# 2-LCD_CAMERA.net
KiCad netlist of a schematic drawn in Altium Designer
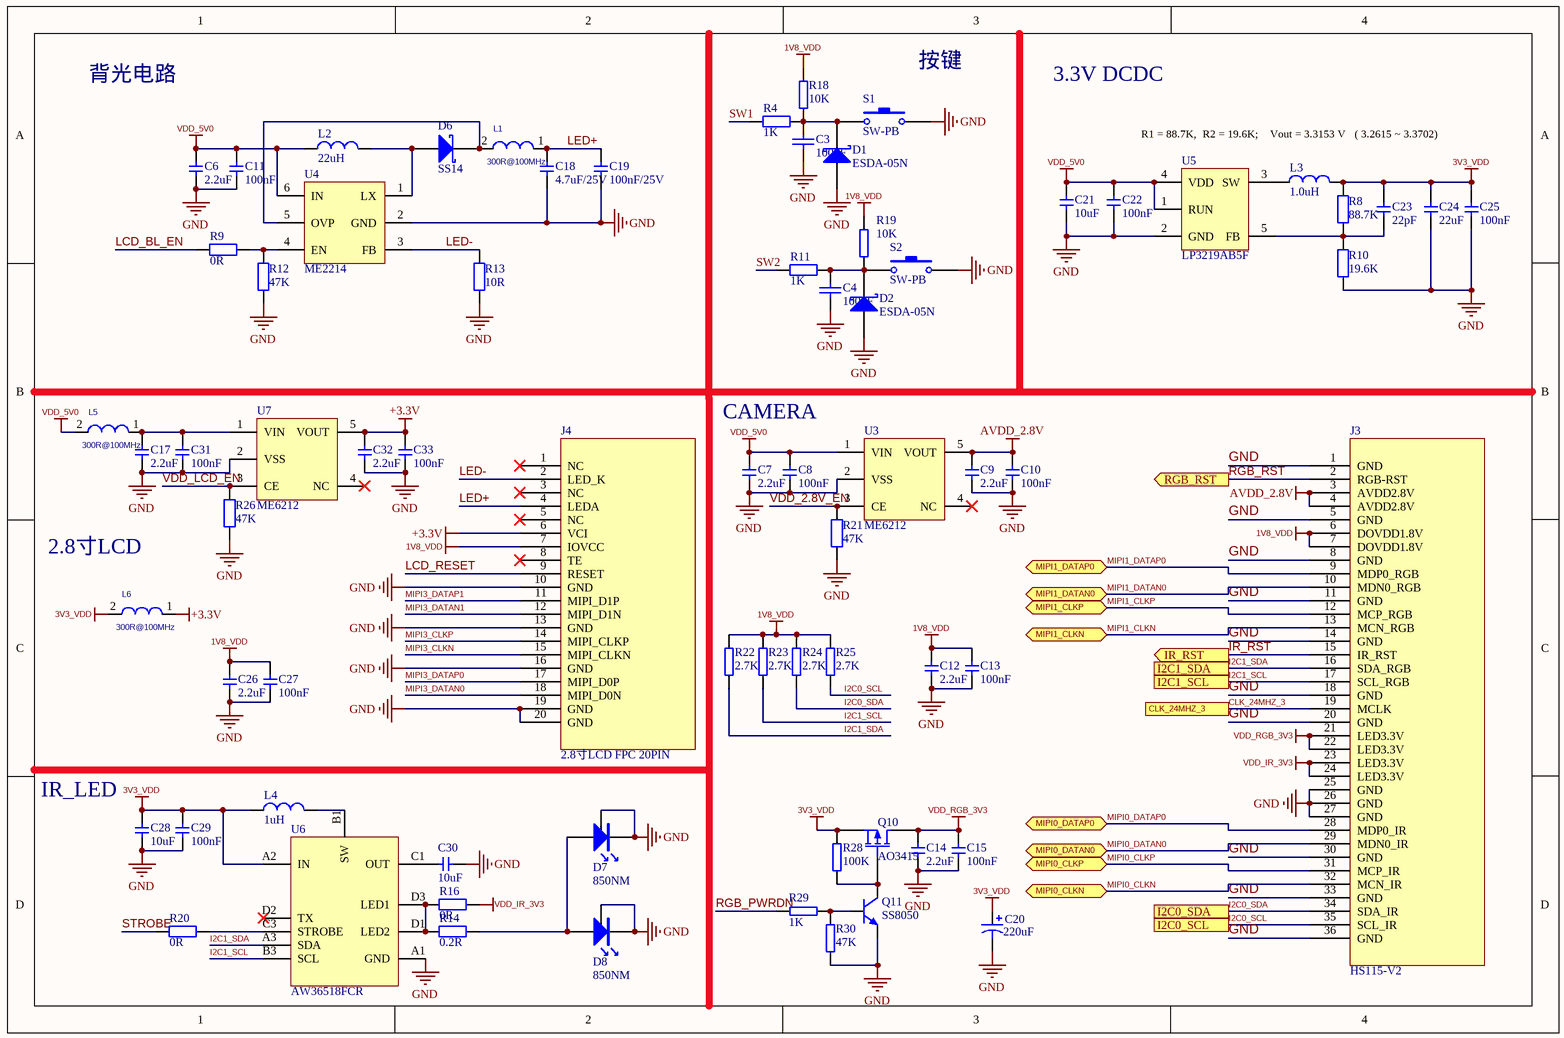
[diagram p0: 2-LCD&CAMERA.SchDoc]

(export (version "E")
  (design (tool "Eeschema 10.0.6"))
  (components
    (comp (ref "C3")
      (value "100nF")
      (footprint "C0402")
      (description "Capacitor")
      (libsource (lib "LORATEMPSENSOR_V0.02") (part "Cap"))
    )
    (comp (ref "C4")
      (value "100nF")
      (footprint "C0402")
      (description "Capacitor")
      (libsource (lib "LORATEMPSENSOR_V0.02") (part "Cap"))
    )
    (comp (ref "C6")
      (value "2.2uF")
      (footprint "C0402")
      (description "C?")
      (libsource (lib "HNCY_SCH_Lib") (part "CAP1"))
    )
    (comp (ref "C7")
      (value "2.2uF")
      (footprint "C0402")
      (description "C?")
      (libsource (lib "HNCY_SCH_Lib") (part "CAP1"))
    )
    (comp (ref "C8")
      (value "100nF")
      (footprint "C0402")
      (description "C?")
      (libsource (lib "HNCY_SCH_Lib") (part "CAP1"))
    )
    (comp (ref "C9")
      (value "2.2uF")
      (footprint "C0402")
      (description "C?")
      (libsource (lib "HNCY_SCH_Lib") (part "CAP1"))
    )
    (comp (ref "C10")
      (value "100nF")
      (footprint "C0402")
      (description "C?")
      (libsource (lib "HNCY_SCH_Lib") (part "CAP1"))
    )
    (comp (ref "C11")
      (value "100nF")
      (footprint "C0402")
      (description "C?")
      (libsource (lib "HNCY_SCH_Lib") (part "CAP1"))
    )
    (comp (ref "C12")
      (value "2.2uF")
      (footprint "C0402")
      (description "C?")
      (libsource (lib "HNCY_SCH_Lib") (part "CAP1"))
    )
    (comp (ref "C13")
      (value "100nF")
      (footprint "C0402")
      (description "C?")
      (libsource (lib "HNCY_SCH_Lib") (part "CAP1"))
    )
    (comp (ref "C14")
      (value "2.2uF")
      (footprint "C0402")
      (description "C?")
      (libsource (lib "HNCY_SCH_Lib") (part "CAP1"))
    )
    (comp (ref "C15")
      (value "100nF")
      (footprint "C0402")
      (description "C?")
      (libsource (lib "HNCY_SCH_Lib") (part "CAP1"))
    )
    (comp (ref "C17")
      (value "2.2uF")
      (footprint "C0402")
      (description "C?")
      (libsource (lib "HNCY_SCH_Lib") (part "CAP1"))
    )
    (comp (ref "C18")
      (value "4.7uF/25V")
      (footprint "Cap_0603")
      (description "C?")
      (libsource (lib "HNCY_SCH_Lib") (part "CAP1"))
    )
    (comp (ref "C19")
      (value "100nF/25V")
      (footprint "C0402")
      (description "C?")
      (libsource (lib "HNCY_SCH_Lib") (part "CAP1"))
    )
    (comp (ref "C20")
      (value "220uF")
      (footprint "SMD,6.3x7.7mm")
      (description "Polarized Capacitor (Radial)")
      (fields (field (name "Comment") "Cap Pol1") (field (name "PUBLISHER") "Altium Limited"))
      (libsource (lib "Miscellaneous Devices") (part "Cap Pol1"))
    )
    (comp (ref "C21")
      (value "10uF")
      (footprint "Cap_0603")
      (description "C?")
      (libsource (lib "HNCY_SCH_Lib") (part "CAP1"))
    )
    (comp (ref "C22")
      (value "100nF")
      (footprint "C0402")
      (description "C?")
      (libsource (lib "HNCY_SCH_Lib") (part "CAP1"))
    )
    (comp (ref "C23")
      (value "22pF")
      (footprint "C0402")
      (description "C?")
      (libsource (lib "HNCY_SCH_Lib") (part "CAP1"))
    )
    (comp (ref "C24")
      (value "22uF")
      (footprint "CAP_0603")
      (description "C?")
      (libsource (lib "HNCY_SCH_Lib") (part "CAP1"))
    )
    (comp (ref "C25")
      (value "100nF")
      (footprint "C0402")
      (description "C?")
      (libsource (lib "HNCY_SCH_Lib") (part "CAP1"))
    )
    (comp (ref "C26")
      (value "2.2uF")
      (footprint "C0402")
      (description "C?")
      (libsource (lib "HNCY_SCH_Lib") (part "CAP1"))
    )
    (comp (ref "C27")
      (value "100nF")
      (footprint "C0402")
      (description "C?")
      (libsource (lib "HNCY_SCH_Lib") (part "CAP1"))
    )
    (comp (ref "C28")
      (value "10uF")
      (footprint "C0402")
      (description "C?")
      (libsource (lib "HNCY_SCH_Lib") (part "CAP1"))
    )
    (comp (ref "C29")
      (value "100nF")
      (footprint "C0402")
      (description "C?")
      (libsource (lib "HNCY_SCH_Lib") (part "CAP1"))
    )
    (comp (ref "C30")
      (value "10uF")
      (footprint "C0402")
      (description "C?")
      (libsource (lib "HNCY_SCH_Lib") (part "CAP1"))
    )
    (comp (ref "C31")
      (value "100nF")
      (footprint "C0402")
      (description "C?")
      (libsource (lib "HNCY_SCH_Lib") (part "CAP1"))
    )
    (comp (ref "C32")
      (value "2.2uF")
      (footprint "C0402")
      (description "C?")
      (libsource (lib "HNCY_SCH_Lib") (part "CAP1"))
    )
    (comp (ref "C33")
      (value "100nF")
      (footprint "C0402")
      (description "C?")
      (libsource (lib "HNCY_SCH_Lib") (part "CAP1"))
    )
    (comp (ref "D1")
      (value "ESDA-05N")
      (footprint "R0402")
      (description "Silicon AF Schottky Diode for High-Speed Switching")
      (fields (field (name "PUBLISHER") "Altium Limited"))
      (libsource (lib "Miscellaneous Devices") (part "Diode BAS70"))
    )
    (comp (ref "D2")
      (value "ESDA-05N")
      (footprint "R0402")
      (description "Silicon AF Schottky Diode for High-Speed Switching")
      (fields (field (name "PUBLISHER") "Altium Limited"))
      (libsource (lib "Miscellaneous Devices") (part "Diode BAS70"))
    )
    (comp (ref "D6")
      (value "SS14")
      (footprint "SOD-123F")
      (description "Silicon AF Schottky Diode for High-Speed Switching")
      (fields (field (name "PUBLISHER") "Altium Limited"))
      (libsource (lib "Miscellaneous Devices") (part "Diode BAS70"))
    )
    (comp (ref "D7")
      (value "850NM")
      (footprint "LED-3535-850MM")
      (description "贴片LED，3535，红外850NM")
      (libsource (lib "MY SCHLIB") (part "LED_IR"))
    )
    (comp (ref "D8")
      (value "850NM")
      (footprint "LED-3535-850MM")
      (description "贴片LED，3535，红外850NM")
      (libsource (lib "Common") (part "LED_IR"))
    )
    (comp (ref "J3")
      (value "HS115-V2")
      (footprint "0.5-36PIN")
      (libsource (lib "MY SCHLIB") (part "HS115-V2"))
    )
    (comp (ref "J4")
      (value "2.8寸LCD FPC 20PIN")
      (footprint "0.5-20PIN-抽屉上接")
      (description "1-Lane MIPI")
      (libsource (lib "MY SCHLIB") (part "2.8寸LCD FPC 20PIN"))
    )
    (comp (ref "L1") (value "300R@100MHz") (footprint "Res_0603") (libsource (lib "*") (part "L/0402")))
    (comp (ref "L2") (value "22uH") (footprint "L3*3") (libsource (lib "封装") (part "LineInductors")))
    (comp (ref "L3")
      (value "1.0uH")
      (footprint "L2.5x2.0x1.0mm")
      (libsource (lib "封装") (part "LineInductors"))
    )
    (comp (ref "L4") (value "1uH") (footprint "L2.5x2.0x1.0mm") (libsource (lib "封装") (part "LineInductors")))
    (comp (ref "L5") (value "300R@100MHz") (footprint "Res_0603") (libsource (lib "*") (part "L/0402")))
    (comp (ref "L6") (value "300R@100MHz") (footprint "Res_0603") (libsource (lib "*") (part "L/0402")))
    (comp (ref "Q10") (value "AO3415") (footprint "SOT-23") (libsource (lib "*") (part "AO3415")))
    (comp (ref "Q11")
      (value "SS8050")
      (footprint "SOT23-BEC")
      (description "贴片三极管")
      (libsource (lib "HNCY_SCH_Lib") (part "NPN"))
    )
    (comp (ref "R4")
      (value "1K")
      (footprint "R0402")
      (description "Resistor")
      (fields (field (name "PUBLISHER") "Altium Limited"))
      (libsource (lib "") (part "Res2_1"))
    )
    (comp (ref "R8")
      (value "88.7K")
      (footprint "R0402")
      (description "Resistor")
      (fields (field (name "PUBLISHER") "Altium Limited"))
      (libsource (lib "Miscellaneous Devices") (part "Res2"))
    )
    (comp (ref "R9")
      (value "0R")
      (footprint "R0402")
      (description "Resistor")
      (fields (field (name "PUBLISHER") "Altium Limited"))
      (libsource (lib "") (part "Res2_1"))
    )
    (comp (ref "R10")
      (value "19.6K")
      (footprint "R0402")
      (description "Resistor")
      (fields (field (name "PUBLISHER") "Altium Limited"))
      (libsource (lib "") (part "Res2_2"))
    )
    (comp (ref "R11")
      (value "1K")
      (footprint "R0402")
      (description "Resistor")
      (fields (field (name "PUBLISHER") "Altium Limited"))
      (libsource (lib "") (part "Res2_1"))
    )
    (comp (ref "R12")
      (value "47K")
      (footprint "R0402")
      (description "Resistor")
      (fields (field (name "PUBLISHER") "Altium Limited"))
      (libsource (lib "Miscellaneous Devices") (part "Res2"))
    )
    (comp (ref "R13")
      (value "10R")
      (footprint "R0805")
      (description "Resistor")
      (fields (field (name "PUBLISHER") "Altium Limited"))
      (libsource (lib "") (part "Res2_2"))
    )
    (comp (ref "R14")
      (value "0.2R")
      (footprint "R0805")
      (description "Resistor")
      (fields (field (name "PUBLISHER") "Altium Limited"))
      (libsource (lib "") (part "Res2_1"))
    )
    (comp (ref "R16")
      (value "0R")
      (footprint "R0805")
      (description "Resistor")
      (fields (field (name "PUBLISHER") "Altium Limited"))
      (libsource (lib "") (part "Res2_1"))
    )
    (comp (ref "R18")
      (value "10K")
      (footprint "R0402")
      (description "R?")
      (libsource (lib "HNCY_SCH_Lib") (part "RES1"))
    )
    (comp (ref "R19")
      (value "10K")
      (footprint "R0402")
      (description "R?")
      (libsource (lib "HNCY_SCH_Lib") (part "RES1"))
    )
    (comp (ref "R20")
      (value "0R")
      (footprint "R0402")
      (description "Resistor")
      (fields (field (name "PUBLISHER") "Altium Limited"))
      (libsource (lib "") (part "Res2_1"))
    )
    (comp (ref "R21")
      (value "47K")
      (footprint "R0402")
      (description "Resistor")
      (fields (field (name "PUBLISHER") "Altium Limited"))
      (libsource (lib "Miscellaneous Devices") (part "Res2"))
    )
    (comp (ref "R22")
      (value "2.7K")
      (footprint "R0402")
      (description "R?")
      (libsource (lib "HNCY_SCH_Lib") (part "RES1"))
    )
    (comp (ref "R23")
      (value "2.7K")
      (footprint "R0402")
      (description "R?")
      (libsource (lib "HNCY_SCH_Lib") (part "RES1"))
    )
    (comp (ref "R24")
      (value "2.7K")
      (footprint "R0402")
      (description "R?")
      (libsource (lib "HNCY_SCH_Lib") (part "RES1"))
    )
    (comp (ref "R25")
      (value "2.7K")
      (footprint "R0402")
      (description "R?")
      (libsource (lib "HNCY_SCH_Lib") (part "RES1"))
    )
    (comp (ref "R26")
      (value "47K")
      (footprint "R0402")
      (description "Resistor")
      (fields (field (name "PUBLISHER") "Altium Limited"))
      (libsource (lib "Miscellaneous Devices") (part "Res2"))
    )
    (comp (ref "R28")
      (value "100K")
      (footprint "R0402")
      (description "R?")
      (libsource (lib "HNCY_SCH_Lib") (part "RES1"))
    )
    (comp (ref "R29")
      (value "1K")
      (footprint "R0402")
      (description "R?")
      (libsource (lib "HNCY_SCH_Lib") (part "RES1"))
    )
    (comp (ref "R30")
      (value "47K")
      (footprint "R0402")
      (description "R?")
      (libsource (lib "HNCY_SCH_Lib") (part "RES1"))
    )
    (comp (ref "S1")
      (value "SW-PB")
      (footprint "轻触开关4.5x4.5")
      (description "Switch")
      (fields (field (name "PUBLISHER") "Altium Limited"))
      (libsource (lib "Miscellaneous Devices") (part "SW-PB"))
    )
    (comp (ref "S2")
      (value "SW-PB")
      (footprint "轻触开关4.5x4.5")
      (description "Switch")
      (fields (field (name "PUBLISHER") "Altium Limited"))
      (libsource (lib "Miscellaneous Devices") (part "SW-PB"))
    )
    (comp (ref "U3") (value "ME6212") (footprint "SOT23-5") (libsource (lib "MY SCHLIB") (part "ME6212")))
    (comp (ref "U4") (value "ME2214") (footprint "SOT26") (libsource (lib "MY SCHLIB") (part "ME2214")))
    (comp (ref "U5") (value "LP3219AB5F") (footprint "SOT23-5") (libsource (lib "MY SCHLIB") (part "TD6817")))
    (comp (ref "U6")
      (value "AW36518FCR")
      (footprint "FCQFN-10L")
      (libsource (lib "MY SCHLIB") (part "AW36518FCR"))
    )
    (comp (ref "U7") (value "ME6212") (footprint "SOT23-5") (libsource (lib "MY SCHLIB") (part "ME6212")))
  )
  (nets
    (net (code "1") (name "+3.3V") (class "Default")
      (node (ref "C32") (pin "1") (pintype "passive"))
      (node (ref "C33") (pin "1") (pintype "passive"))
      (node (ref "J4") (pin "6") (pinfunction "VCI_6") (pintype "passive"))
      (node (ref "L6") (pin "1") (pinfunction "1_1") (pintype "passive"))
      (node (ref "U7") (pin "5") (pinfunction "VOUT_5") (pintype "passive"))
    )
    (net (code "2") (name "/CLK_24MHZ_3") (class "Default")
      (node (ref "J3") (pin "19") (pinfunction "MCLK_19") (pintype "passive"))
    )
    (net (code "3") (name "/I2C0_SCL") (class "Default")
      (node (ref "J3") (pin "35") (pinfunction "SCL_IR_35") (pintype "passive"))
      (node (ref "R25") (pin "2") (pinfunction "2_2") (pintype "passive"))
    )
    (net (code "4") (name "/I2C0_SDA") (class "Default")
      (node (ref "J3") (pin "34") (pinfunction "SDA_IR_34") (pintype "passive"))
      (node (ref "R24") (pin "2") (pinfunction "2_2") (pintype "passive"))
    )
    (net (code "5") (name "/I2C1_SCL") (class "Default")
      (node (ref "J3") (pin "17") (pinfunction "SCL_RGB_17") (pintype "passive"))
      (node (ref "R23") (pin "2") (pinfunction "2_2") (pintype "passive"))
      (node (ref "U6") (pin "B3") (pinfunction "SCL_B3") (pintype "passive"))
    )
    (net (code "6") (name "/I2C1_SDA") (class "Default")
      (node (ref "J3") (pin "16") (pinfunction "SDA_RGB_16") (pintype "passive"))
      (node (ref "R22") (pin "2") (pinfunction "2_2") (pintype "passive"))
      (node (ref "U6") (pin "A3") (pinfunction "SDA_A3") (pintype "passive"))
    )
    (net (code "7") (name "/IR_RST") (class "Default")
      (node (ref "J3") (pin "15") (pinfunction "IR_RST_15") (pintype "passive"))
    )
    (net (code "8") (name "/LCD_BL_EN") (class "Default")
      (node (ref "R9") (pin "1") (pinfunction "1_1") (pintype "passive"))
    )
    (net (code "9") (name "/LCD_RESET") (class "Default")
      (node (ref "J4") (pin "9") (pinfunction "RESET_9") (pintype "passive"))
    )
    (net (code "10") (name "/LED+") (class "Default")
      (node (ref "C18") (pin "1") (pintype "passive"))
      (node (ref "C19") (pin "1") (pintype "passive"))
      (node (ref "J4") (pin "4") (pinfunction "LEDA_4") (pintype "passive"))
      (node (ref "L1") (pin "1") (pinfunction "1_1") (pintype "passive"))
    )
    (net (code "11") (name "/LED-") (class "Default")
      (node (ref "J4") (pin "2") (pinfunction "LED_K_2") (pintype "passive"))
      (node (ref "R13") (pin "1") (pinfunction "1_1") (pintype "passive"))
      (node (ref "U4") (pin "3") (pinfunction "FB_3") (pintype "passive"))
    )
    (net (code "12") (name "/MIPI0_CLKN") (class "Default")
      (node (ref "J3") (pin "32") (pinfunction "MCN_IR_32") (pintype "passive"))
    )
    (net (code "13") (name "/MIPI0_CLKP") (class "Default")
      (node (ref "J3") (pin "31") (pinfunction "MCP_IR_31") (pintype "passive"))
    )
    (net (code "14") (name "/MIPI0_DATAN0") (class "Default")
      (node (ref "J3") (pin "29") (pinfunction "MDN0_IR_29") (pintype "passive"))
    )
    (net (code "15") (name "/MIPI0_DATAP0") (class "Default")
      (node (ref "J3") (pin "28") (pinfunction "MDP0_IR_28") (pintype "passive"))
    )
    (net (code "16") (name "/MIPI1_CLKN") (class "Default")
      (node (ref "J3") (pin "13") (pinfunction "MCN_RGB_13") (pintype "passive"))
    )
    (net (code "17") (name "/MIPI1_CLKP") (class "Default")
      (node (ref "J3") (pin "12") (pinfunction "MCP_RGB_12") (pintype "passive"))
    )
    (net (code "18") (name "/MIPI1_DATAN0") (class "Default")
      (node (ref "J3") (pin "10") (pinfunction "MDN0_RGB_10") (pintype "passive"))
    )
    (net (code "19") (name "/MIPI1_DATAP0") (class "Default")
      (node (ref "J3") (pin "9") (pinfunction "MDP0_RGB_9") (pintype "passive"))
    )
    (net (code "20") (name "/MIPI3_CLKN") (class "Default")
      (node (ref "J4") (pin "15") (pinfunction "MIPI_CLKN_15") (pintype "passive"))
    )
    (net (code "21") (name "/MIPI3_CLKP") (class "Default")
      (node (ref "J4") (pin "14") (pinfunction "MIPI_CLKP_14") (pintype "passive"))
    )
    (net (code "22") (name "/MIPI3_DATAN0") (class "Default")
      (node (ref "J4") (pin "18") (pinfunction "MIPI_D0N_18") (pintype "passive"))
    )
    (net (code "23") (name "/MIPI3_DATAN1") (class "Default")
      (node (ref "J4") (pin "12") (pinfunction "MIPI_D1N_12") (pintype "passive"))
    )
    (net (code "24") (name "/MIPI3_DATAP0") (class "Default")
      (node (ref "J4") (pin "17") (pinfunction "MIPI_D0P_17") (pintype "passive"))
    )
    (net (code "25") (name "/MIPI3_DATAP1") (class "Default")
      (node (ref "J4") (pin "11") (pinfunction "MIPI_D1P_11") (pintype "passive"))
    )
    (net (code "26") (name "/RGB_PWRDN") (class "Default")
      (node (ref "R29") (pin "2") (pinfunction "2_2") (pintype "passive"))
    )
    (net (code "27") (name "/RGB_RST") (class "Default")
      (node (ref "J3") (pin "2") (pinfunction "RGB-RST_2") (pintype "passive"))
    )
    (net (code "28") (name "/STROBE") (class "Default")
      (node (ref "R20") (pin "1") (pinfunction "1_1") (pintype "passive"))
    )
    (net (code "29") (name "/SW1") (class "Default")
      (node (ref "R4") (pin "1") (pinfunction "1_1") (pintype "passive"))
    )
    (net (code "30") (name "/SW2") (class "Default")
      (node (ref "R11") (pin "1") (pinfunction "1_1") (pintype "passive"))
    )
    (net (code "31") (name "/VDD_2.8V_EN") (class "Default")
      (node (ref "R21") (pin "2") (pinfunction "2_2") (pintype "passive"))
      (node (ref "U3") (pin "3") (pinfunction "CE_3") (pintype "passive"))
    )
    (net (code "32") (name "/VDD_LCD_EN") (class "Default")
      (node (ref "R26") (pin "2") (pinfunction "2_2") (pintype "passive"))
      (node (ref "U7") (pin "3") (pinfunction "CE_3") (pintype "passive"))
    )
    (net (code "33") (name "1V8_VDD") (class "Default")
      (node (ref "C12") (pin "1") (pintype "passive"))
      (node (ref "C13") (pin "1") (pintype "passive"))
      (node (ref "C26") (pin "1") (pintype "passive"))
      (node (ref "C27") (pin "1") (pintype "passive"))
      (node (ref "J3") (pin "6") (pinfunction "DOVDD1.8V_6") (pintype "passive"))
      (node (ref "J3") (pin "7") (pinfunction "DOVDD1.8V_7") (pintype "passive"))
      (node (ref "J4") (pin "7") (pinfunction "IOVCC_7") (pintype "passive"))
      (node (ref "R18") (pin "2") (pinfunction "2_2") (pintype "passive"))
      (node (ref "R19") (pin "2") (pinfunction "2_2") (pintype "passive"))
      (node (ref "R22") (pin "1") (pinfunction "1_1") (pintype "passive"))
      (node (ref "R23") (pin "1") (pinfunction "1_1") (pintype "passive"))
      (node (ref "R24") (pin "1") (pinfunction "1_1") (pintype "passive"))
      (node (ref "R25") (pin "1") (pinfunction "1_1") (pintype "passive"))
    )
    (net (code "34") (name "3V3_VDD") (class "Default")
      (node (ref "C20") (pin "1") (pinfunction "1_1") (pintype "passive"))
      (node (ref "C23") (pin "2") (pintype "passive"))
      (node (ref "C24") (pin "1") (pintype "passive"))
      (node (ref "C25") (pin "1") (pintype "passive"))
      (node (ref "C28") (pin "1") (pintype "passive"))
      (node (ref "C29") (pin "1") (pintype "passive"))
      (node (ref "L3") (pin "2") (pinfunction "2_2") (pintype "passive"))
      (node (ref "L4") (pin "1") (pinfunction "1_1") (pintype "passive"))
      (node (ref "L6") (pin "2") (pinfunction "2_2") (pintype "passive"))
      (node (ref "Q10") (pin "2") (pinfunction "S_2") (pintype "passive"))
      (node (ref "R28") (pin "2") (pinfunction "2_2") (pintype "passive"))
      (node (ref "R8") (pin "2") (pinfunction "2_2") (pintype "passive"))
      (node (ref "U6") (pin "A2") (pinfunction "IN_A2") (pintype "passive"))
    )
    (net (code "35") (name "AVDD_2.8V") (class "Default")
      (node (ref "C10") (pin "1") (pintype "passive"))
      (node (ref "C9") (pin "1") (pintype "passive"))
      (node (ref "J3") (pin "3") (pinfunction "AVDD2.8V_3") (pintype "passive"))
      (node (ref "J3") (pin "4") (pinfunction "AVDD2.8V_4") (pintype "passive"))
      (node (ref "U3") (pin "5") (pinfunction "VOUT_5") (pintype "passive"))
    )
    (net (code "36") (name "GND") (class "Default")
      (node (ref "C10") (pin "2") (pintype "passive"))
      (node (ref "C11") (pin "2") (pintype "passive"))
      (node (ref "C12") (pin "2") (pintype "passive"))
      (node (ref "C13") (pin "2") (pintype "passive"))
      (node (ref "C14") (pin "2") (pintype "passive"))
      (node (ref "C15") (pin "2") (pintype "passive"))
      (node (ref "C17") (pin "2") (pintype "passive"))
      (node (ref "C18") (pin "2") (pintype "passive"))
      (node (ref "C19") (pin "2") (pintype "passive"))
      (node (ref "C20") (pin "2") (pinfunction "2_2") (pintype "passive"))
      (node (ref "C21") (pin "2") (pintype "passive"))
      (node (ref "C22") (pin "2") (pintype "passive"))
      (node (ref "C24") (pin "2") (pintype "passive"))
      (node (ref "C25") (pin "2") (pintype "passive"))
      (node (ref "C26") (pin "2") (pintype "passive"))
      (node (ref "C27") (pin "2") (pintype "passive"))
      (node (ref "C28") (pin "2") (pintype "passive"))
      (node (ref "C29") (pin "2") (pintype "passive"))
      (node (ref "C3") (pin "2") (pinfunction "2_2") (pintype "passive"))
      (node (ref "C30") (pin "2") (pintype "passive"))
      (node (ref "C31") (pin "2") (pintype "passive"))
      (node (ref "C32") (pin "2") (pintype "passive"))
      (node (ref "C33") (pin "2") (pintype "passive"))
      (node (ref "C4") (pin "2") (pinfunction "2_2") (pintype "passive"))
      (node (ref "C6") (pin "2") (pintype "passive"))
      (node (ref "C7") (pin "2") (pintype "passive"))
      (node (ref "C8") (pin "2") (pintype "passive"))
      (node (ref "C9") (pin "2") (pintype "passive"))
      (node (ref "D1") (pin "1") (pinfunction "A_1") (pintype "passive"))
      (node (ref "D2") (pin "1") (pinfunction "A_1") (pintype "passive"))
      (node (ref "D7") (pin "0") (pinfunction "0_0") (pintype "passive"))
      (node (ref "D7") (pin "K") (pinfunction "K_K") (pintype "passive"))
      (node (ref "D8") (pin "0") (pinfunction "0_0") (pintype "passive"))
      (node (ref "D8") (pin "K") (pinfunction "K_K") (pintype "passive"))
      (node (ref "J3") (pin "1") (pinfunction "GND_1") (pintype "passive"))
      (node (ref "J3") (pin "11") (pinfunction "GND_11") (pintype "passive"))
      (node (ref "J3") (pin "14") (pinfunction "GND_14") (pintype "passive"))
      (node (ref "J3") (pin "18") (pinfunction "GND_18") (pintype "passive"))
      (node (ref "J3") (pin "20") (pinfunction "GND_20") (pintype "passive"))
      (node (ref "J3") (pin "25") (pinfunction "GND_25") (pintype "passive"))
      (node (ref "J3") (pin "26") (pinfunction "GND_26") (pintype "passive"))
      (node (ref "J3") (pin "27") (pinfunction "GND_27") (pintype "passive"))
      (node (ref "J3") (pin "30") (pinfunction "GND_30") (pintype "passive"))
      (node (ref "J3") (pin "33") (pinfunction "GND_33") (pintype "passive"))
      (node (ref "J3") (pin "36") (pinfunction "GND_36") (pintype "passive"))
      (node (ref "J3") (pin "5") (pinfunction "GND_5") (pintype "passive"))
      (node (ref "J3") (pin "8") (pinfunction "GND_8") (pintype "passive"))
      (node (ref "J4") (pin "10") (pinfunction "GND_10") (pintype "passive"))
      (node (ref "J4") (pin "13") (pinfunction "GND_13") (pintype "passive"))
      (node (ref "J4") (pin "16") (pinfunction "GND_16") (pintype "passive"))
      (node (ref "J4") (pin "19") (pinfunction "GND_19") (pintype "passive"))
      (node (ref "J4") (pin "20") (pinfunction "GND_20") (pintype "passive"))
      (node (ref "Q11") (pin "E") (pinfunction "E_E") (pintype "passive"))
      (node (ref "R10") (pin "2") (pinfunction "2_2") (pintype "passive"))
      (node (ref "R12") (pin "1") (pinfunction "1_1") (pintype "passive"))
      (node (ref "R13") (pin "2") (pinfunction "2_2") (pintype "passive"))
      (node (ref "R21") (pin "1") (pinfunction "1_1") (pintype "passive"))
      (node (ref "R26") (pin "1") (pinfunction "1_1") (pintype "passive"))
      (node (ref "R30") (pin "2") (pinfunction "2_2") (pintype "passive"))
      (node (ref "S1") (pin "2") (pinfunction "2_2") (pintype "passive"))
      (node (ref "S2") (pin "2") (pinfunction "2_2") (pintype "passive"))
      (node (ref "U3") (pin "2") (pinfunction "VSS_2") (pintype "passive"))
      (node (ref "U4") (pin "2") (pinfunction "GND_2") (pintype "passive"))
      (node (ref "U5") (pin "2") (pinfunction "GND_2") (pintype "passive"))
      (node (ref "U6") (pin "A1") (pinfunction "GND_A1") (pintype "passive"))
      (node (ref "U7") (pin "2") (pinfunction "VSS_2") (pintype "passive"))
    )
    (net (code "37") (name "Net-(D1-K)") (class "Default")
      (node (ref "C3") (pin "1") (pinfunction "1_1") (pintype "passive"))
      (node (ref "D1") (pin "2") (pinfunction "K_2") (pintype "passive"))
      (node (ref "R18") (pin "1") (pinfunction "1_1") (pintype "passive"))
      (node (ref "R4") (pin "2") (pinfunction "2_2") (pintype "passive"))
      (node (ref "S1") (pin "1") (pinfunction "1_1") (pintype "passive"))
    )
    (net (code "38") (name "Net-(D2-K)") (class "Default")
      (node (ref "C4") (pin "1") (pinfunction "1_1") (pintype "passive"))
      (node (ref "D2") (pin "2") (pinfunction "K_2") (pintype "passive"))
      (node (ref "R11") (pin "2") (pinfunction "2_2") (pintype "passive"))
      (node (ref "R19") (pin "1") (pinfunction "1_1") (pintype "passive"))
      (node (ref "S2") (pin "1") (pinfunction "1_1") (pintype "passive"))
    )
    (net (code "39") (name "Net-(D6-A)") (class "Default")
      (node (ref "D6") (pin "1") (pinfunction "A_1") (pintype "passive"))
      (node (ref "L2") (pin "2") (pinfunction "2_2") (pintype "passive"))
      (node (ref "U4") (pin "1") (pinfunction "LX_1") (pintype "passive"))
    )
    (net (code "40") (name "Net-(D6-K)") (class "Default")
      (node (ref "D6") (pin "2") (pinfunction "K_2") (pintype "passive"))
      (node (ref "L1") (pin "2") (pinfunction "2_2") (pintype "passive"))
      (node (ref "U4") (pin "5") (pinfunction "OVP_5") (pintype "passive"))
    )
    (net (code "41") (name "Net-(D7-PadA)") (class "Default")
      (node (ref "D7") (pin "A") (pinfunction "A_A") (pintype "passive"))
      (node (ref "D8") (pin "A") (pinfunction "A_A") (pintype "passive"))
      (node (ref "R14") (pin "2") (pinfunction "2_2") (pintype "passive"))
    )
    (net (code "42") (name "Net-(Q10-G)") (class "Default")
      (node (ref "Q10") (pin "1") (pinfunction "G_1") (pintype "passive"))
      (node (ref "Q11") (pin "C") (pinfunction "C_C") (pintype "passive"))
      (node (ref "R28") (pin "1") (pinfunction "1_1") (pintype "passive"))
    )
    (net (code "43") (name "Net-(Q11-PadB)") (class "Default")
      (node (ref "Q11") (pin "B") (pinfunction "B_B") (pintype "passive"))
      (node (ref "R29") (pin "1") (pinfunction "1_1") (pintype "passive"))
      (node (ref "R30") (pin "1") (pinfunction "1_1") (pintype "passive"))
    )
    (net (code "44") (name "Net-(U4-EN)") (class "Default")
      (node (ref "R12") (pin "2") (pinfunction "2_2") (pintype "passive"))
      (node (ref "R9") (pin "2") (pinfunction "2_2") (pintype "passive"))
      (node (ref "U4") (pin "4") (pinfunction "EN_4") (pintype "passive"))
    )
    (net (code "45") (name "Net-(U5-FB)") (class "Default")
      (node (ref "C23") (pin "1") (pintype "passive"))
      (node (ref "R10") (pin "1") (pinfunction "1_1") (pintype "passive"))
      (node (ref "R8") (pin "1") (pinfunction "1_1") (pintype "passive"))
      (node (ref "U5") (pin "5") (pinfunction "FB_5") (pintype "passive"))
    )
    (net (code "46") (name "Net-(U5-SW)") (class "Default")
      (node (ref "L3") (pin "1") (pinfunction "1_1") (pintype "passive"))
      (node (ref "U5") (pin "3") (pinfunction "SW_3") (pintype "passive"))
    )
    (net (code "47") (name "Net-(U6-LED1)") (class "Default")
      (node (ref "R14") (pin "1") (pinfunction "1_1") (pintype "passive"))
      (node (ref "R16") (pin "1") (pinfunction "1_1") (pintype "passive"))
      (node (ref "U6") (pin "D1") (pinfunction "LED2_D1") (pintype "passive"))
      (node (ref "U6") (pin "D3") (pinfunction "LED1_D3") (pintype "passive"))
    )
    (net (code "48") (name "Net-(U6-OUT)") (class "Default")
      (node (ref "C30") (pin "1") (pintype "passive"))
      (node (ref "U6") (pin "C1") (pinfunction "OUT_C1") (pintype "passive"))
    )
    (net (code "49") (name "Net-(U6-STROBE)") (class "Default")
      (node (ref "R20") (pin "2") (pinfunction "2_2") (pintype "passive"))
      (node (ref "U6") (pin "C3") (pinfunction "STROBE_C3") (pintype "passive"))
    )
    (net (code "50") (name "Net-(U6-SW)") (class "Default")
      (node (ref "L4") (pin "2") (pinfunction "2_2") (pintype "passive"))
      (node (ref "U6") (pin "B1") (pinfunction "SW_B1") (pintype "passive"))
    )
    (net (code "51") (name "Net-(U7-VIN)") (class "Default")
      (node (ref "C17") (pin "1") (pintype "passive"))
      (node (ref "C31") (pin "1") (pintype "passive"))
      (node (ref "L5") (pin "1") (pinfunction "1_1") (pintype "passive"))
      (node (ref "U7") (pin "1") (pinfunction "VIN_1") (pintype "passive"))
    )
    (net (code "52") (name "VDD_5V0") (class "Default")
      (node (ref "C11") (pin "1") (pintype "passive"))
      (node (ref "C21") (pin "1") (pintype "passive"))
      (node (ref "C22") (pin "1") (pintype "passive"))
      (node (ref "C6") (pin "1") (pintype "passive"))
      (node (ref "C7") (pin "1") (pintype "passive"))
      (node (ref "C8") (pin "1") (pintype "passive"))
      (node (ref "L2") (pin "1") (pinfunction "1_1") (pintype "passive"))
      (node (ref "L5") (pin "2") (pinfunction "2_2") (pintype "passive"))
      (node (ref "U3") (pin "1") (pinfunction "VIN_1") (pintype "passive"))
      (node (ref "U4") (pin "6") (pinfunction "IN_6") (pintype "passive"))
      (node (ref "U5") (pin "1") (pinfunction "RUN_1") (pintype "passive"))
      (node (ref "U5") (pin "4") (pinfunction "VDD_4") (pintype "passive"))
    )
    (net (code "53") (name "VDD_IR_3V3") (class "Default")
      (node (ref "J3") (pin "23") (pinfunction "LED3.3V_23") (pintype "passive"))
      (node (ref "J3") (pin "24") (pinfunction "LED3.3V_24") (pintype "passive"))
      (node (ref "R16") (pin "2") (pinfunction "2_2") (pintype "passive"))
    )
    (net (code "54") (name "VDD_RGB_3V3") (class "Default")
      (node (ref "C14") (pin "1") (pintype "passive"))
      (node (ref "C15") (pin "1") (pintype "passive"))
      (node (ref "J3") (pin "21") (pinfunction "LED3.3V_21") (pintype "passive"))
      (node (ref "J3") (pin "22") (pinfunction "LED3.3V_22") (pintype "passive"))
      (node (ref "Q10") (pin "3") (pinfunction "D_3") (pintype "passive"))
    )
    (net (code "55") (name "unconnected-(J4-NC-Pad1)") (class "Default")
      (node (ref "J4") (pin "1") (pinfunction "NC_1") (pintype "passive+no_connect"))
    )
    (net (code "56") (name "unconnected-(J4-NC-Pad3)") (class "Default")
      (node (ref "J4") (pin "3") (pinfunction "NC_3") (pintype "passive+no_connect"))
    )
    (net (code "57") (name "unconnected-(J4-NC-Pad5)") (class "Default")
      (node (ref "J4") (pin "5") (pinfunction "NC_5") (pintype "passive+no_connect"))
    )
    (net (code "58") (name "unconnected-(J4-TE-Pad8)") (class "Default")
      (node (ref "J4") (pin "8") (pinfunction "TE_8") (pintype "passive+no_connect"))
    )
    (net (code "59") (name "unconnected-(U3-NC-Pad4)") (class "Default")
      (node (ref "U3") (pin "4") (pinfunction "NC_4") (pintype "passive+no_connect"))
    )
    (net (code "60") (name "unconnected-(U6-TX-PadD2)") (class "Default")
      (node (ref "U6") (pin "D2") (pinfunction "TX_D2") (pintype "passive+no_connect"))
    )
    (net (code "61") (name "unconnected-(U7-NC-Pad4)") (class "Default")
      (node (ref "U7") (pin "4") (pinfunction "NC_4") (pintype "passive+no_connect"))
    )
  )
)
